# EDA_DriverBoardV1.net
KiCad netlist of a schematic drawn in EasyEDA
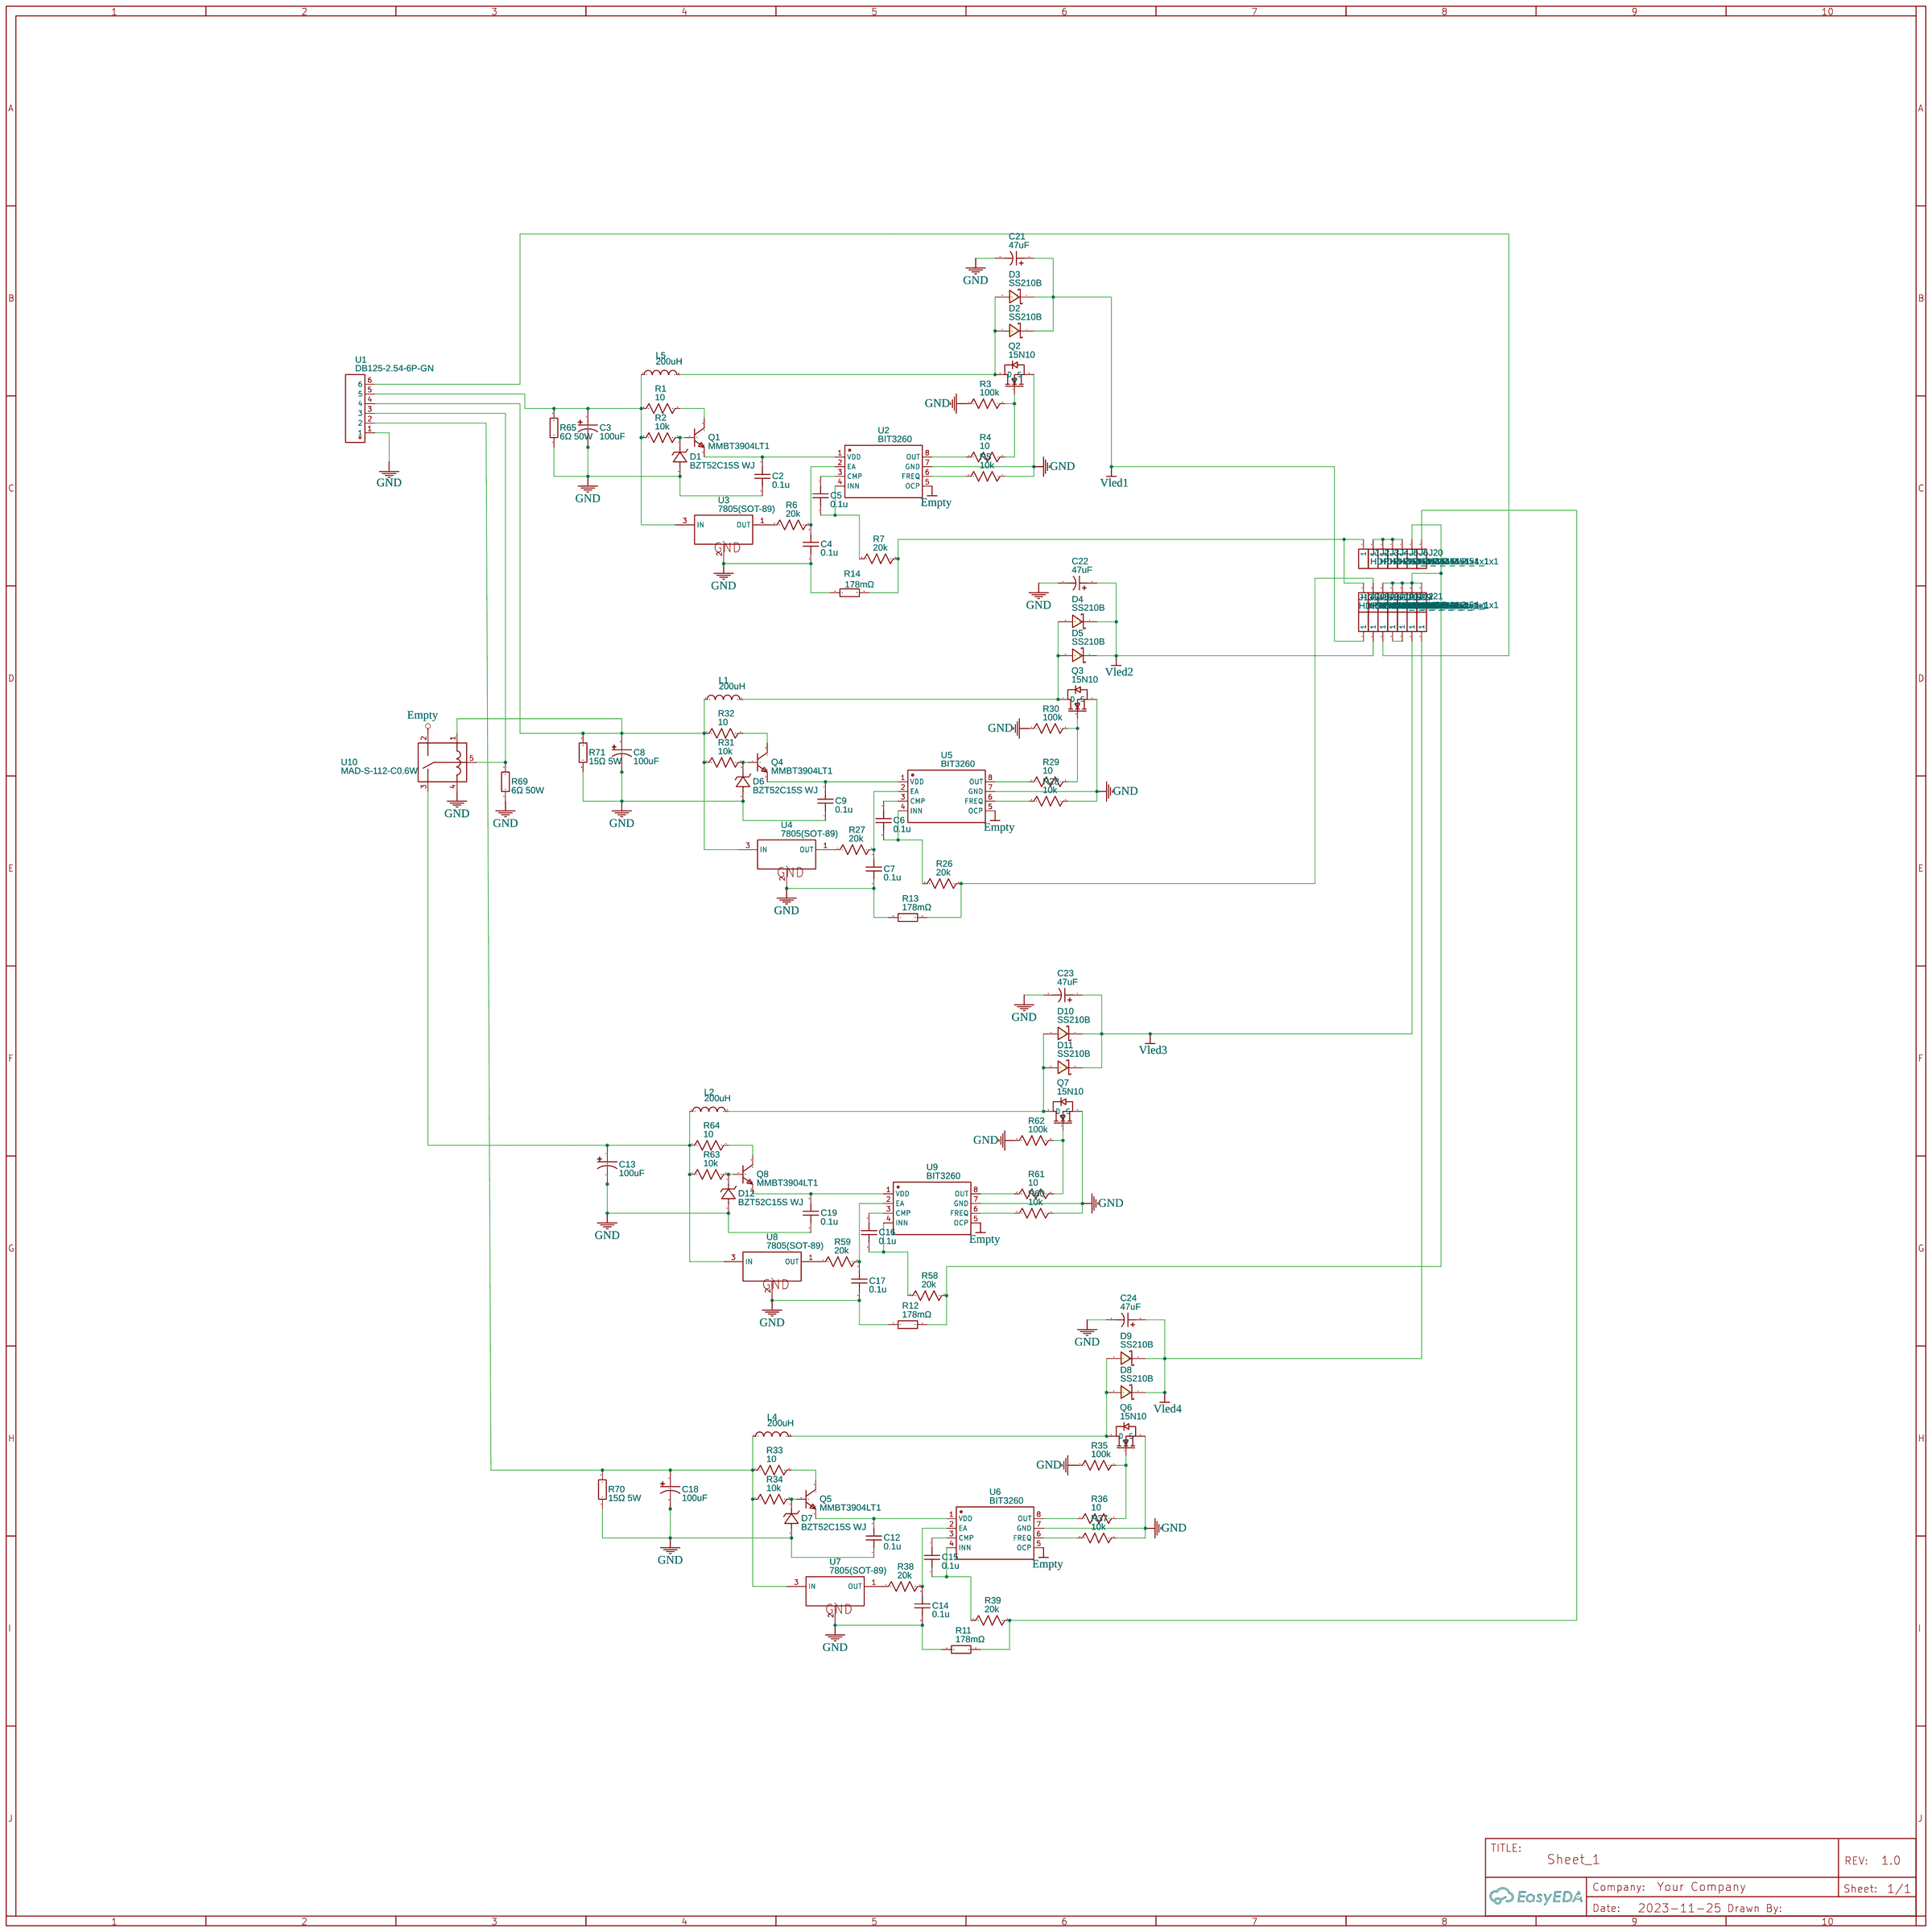
[diagram p0: schematic sheet]

(export (version "E")
  (design (tool "Eeschema 10.0.6"))
  (components
    (comp (ref "C2") (value "0.1u") (libsource (lib "") (part "C_0603_US")))
    (comp (ref "C3")
      (value "100uF")
      (fields
        (field (name "Manufacturer Part") "SPZ1HM101F09O00RAXXX")
        (field (name "Manufacturer") "AISHI(艾华集团)")
      )
      (libsource (lib "") (part "SPZ1HM101F09O00RAXXX_1"))
    )
    (comp (ref "C4") (value "0.1u") (libsource (lib "") (part "C_0603_US")))
    (comp (ref "C5") (value "0.1u") (libsource (lib "") (part "C_0603_US_1")))
    (comp (ref "C6") (value "0.1u") (libsource (lib "") (part "C_0603_US_1")))
    (comp (ref "C7") (value "0.1u") (libsource (lib "") (part "C_0603_US")))
    (comp (ref "C8")
      (value "100uF")
      (fields
        (field (name "Manufacturer Part") "SPZ1HM101F09O00RAXXX")
        (field (name "Manufacturer") "AISHI(艾华集团)")
      )
      (libsource (lib "") (part "SPZ1HM101F09O00RAXXX_1"))
    )
    (comp (ref "C9") (value "0.1u") (libsource (lib "") (part "C_0603_US")))
    (comp (ref "C12") (value "0.1u") (libsource (lib "") (part "C_0603_US")))
    (comp (ref "C13")
      (value "100uF")
      (fields
        (field (name "Manufacturer Part") "SPZ1HM101F09O00RAXXX")
        (field (name "Manufacturer") "AISHI(艾华集团)")
      )
      (libsource (lib "") (part "SPZ1HM101F09O00RAXXX"))
    )
    (comp (ref "C14") (value "0.1u") (libsource (lib "") (part "C_0603_US")))
    (comp (ref "C15") (value "0.1u") (libsource (lib "") (part "C_0603_US_1")))
    (comp (ref "C16") (value "0.1u") (libsource (lib "") (part "C_0603_US_1")))
    (comp (ref "C17") (value "0.1u") (libsource (lib "") (part "C_0603_US")))
    (comp (ref "C18")
      (value "100uF")
      (fields
        (field (name "Manufacturer Part") "SPZ1HM101F09O00RAXXX")
        (field (name "Manufacturer") "AISHI(艾华集团)")
      )
      (libsource (lib "") (part "SPZ1HM101F09O00RAXXX"))
    )
    (comp (ref "C19") (value "0.1u") (libsource (lib "") (part "C_0603_US")))
    (comp (ref "C21")
      (value "47uF")
      (fields
        (field (name "Manufacturer Part") "SPZ1KM470G12O00RAXXX")
        (field (name "Manufacturer") "AISHI(艾华集团)")
      )
      (libsource (lib "") (part "SPZ1KM470G12O00RAXXX_1"))
    )
    (comp (ref "C22")
      (value "47uF")
      (fields
        (field (name "Manufacturer Part") "SPZ1KM470G12O00RAXXX")
        (field (name "Manufacturer") "AISHI(艾华集团)")
      )
      (libsource (lib "") (part "SPZ1KM470G12O00RAXXX_1"))
    )
    (comp (ref "C23")
      (value "47uF")
      (fields
        (field (name "Manufacturer Part") "SPZ1KM470G12O00RAXXX")
        (field (name "Manufacturer") "AISHI(艾华集团)")
      )
      (libsource (lib "") (part "SPZ1KM470G12O00RAXXX"))
    )
    (comp (ref "C24")
      (value "47uF")
      (fields
        (field (name "Manufacturer Part") "SPZ1KM470G12O00RAXXX")
        (field (name "Manufacturer") "AISHI(艾华集团)")
      )
      (libsource (lib "") (part "SPZ1KM470G12O00RAXXX"))
    )
    (comp (ref "D1")
      (value "BZT52C15S WJ")
      (fields (field (name "Manufacturer") "CBI(创基)"))
      (libsource (lib "") (part "BZT52C15S WJ"))
    )
    (comp (ref "D2")
      (value "SS210B")
      (fields (field (name "Manufacturer") "晶导微电子"))
      (libsource (lib "") (part "SS210B"))
    )
    (comp (ref "D3")
      (value "SS210B")
      (fields (field (name "Manufacturer") "晶导微电子"))
      (libsource (lib "") (part "SS210B"))
    )
    (comp (ref "D4")
      (value "SS210B")
      (fields (field (name "Manufacturer") "晶导微电子"))
      (libsource (lib "") (part "SS210B"))
    )
    (comp (ref "D5")
      (value "SS210B")
      (fields (field (name "Manufacturer") "晶导微电子"))
      (libsource (lib "") (part "SS210B"))
    )
    (comp (ref "D6")
      (value "BZT52C15S WJ")
      (fields (field (name "Manufacturer") "CBI(创基)"))
      (libsource (lib "") (part "BZT52C15S WJ"))
    )
    (comp (ref "D7")
      (value "BZT52C15S WJ")
      (fields (field (name "Manufacturer") "CBI(创基)"))
      (libsource (lib "") (part "BZT52C15S WJ"))
    )
    (comp (ref "D8")
      (value "SS210B")
      (fields (field (name "Manufacturer") "晶导微电子"))
      (libsource (lib "") (part "SS210B"))
    )
    (comp (ref "D9")
      (value "SS210B")
      (fields (field (name "Manufacturer") "晶导微电子"))
      (libsource (lib "") (part "SS210B"))
    )
    (comp (ref "D10")
      (value "SS210B")
      (fields (field (name "Manufacturer") "晶导微电子"))
      (libsource (lib "") (part "SS210B"))
    )
    (comp (ref "D11")
      (value "SS210B")
      (fields (field (name "Manufacturer") "晶导微电子"))
      (libsource (lib "") (part "SS210B"))
    )
    (comp (ref "D12")
      (value "BZT52C15S WJ")
      (fields (field (name "Manufacturer") "CBI(创基)"))
      (libsource (lib "") (part "BZT52C15S WJ"))
    )
    (comp (ref "J1") (value "HDR-M-2.54_1x1") (libsource (lib "") (part "HDR-M-2.54_1x1_1")))
    (comp (ref "J2") (value "HDR-M-2.54_1x1") (libsource (lib "") (part "HDR-M-2.54_1x1_1")))
    (comp (ref "J3") (value "HDR-M-2.54_1x1") (libsource (lib "") (part "HDR-M-2.54_1x1_1")))
    (comp (ref "J4") (value "HDR-M-2.54_1x1") (libsource (lib "") (part "HDR-M-2.54_1x1_1")))
    (comp (ref "J5") (value "HDR-M-2.54_1x1") (libsource (lib "") (part "HDR-M-2.54_1x1_1")))
    (comp (ref "J6") (value "HDR-M-2.54_1x1") (libsource (lib "") (part "HDR-M-2.54_1x1_1")))
    (comp (ref "J7") (value "HDR-M-2.54_1x1") (libsource (lib "") (part "HDR-M-2.54_1x1_1")))
    (comp (ref "J8") (value "HDR-M-2.54_1x1") (libsource (lib "") (part "HDR-M-2.54_1x1_1")))
    (comp (ref "J9") (value "HDR-M-2.54_1x1") (libsource (lib "") (part "HDR-M-2.54_1x1_1")))
    (comp (ref "J10") (value "HDR-M-2.54_1x1") (libsource (lib "") (part "HDR-M-2.54_1x1_1")))
    (comp (ref "J11") (value "HDR-M-2.54_1x1") (libsource (lib "") (part "HDR-M-2.54_1x1_1")))
    (comp (ref "J12") (value "HDR-M-2.54_1x1") (libsource (lib "") (part "HDR-M-2.54_1x1_1")))
    (comp (ref "J13") (value "HDR-M-2.54_1x1") (libsource (lib "") (part "HDR-M-2.54_1x1")))
    (comp (ref "J14") (value "HDR-M-2.54_1x1") (libsource (lib "") (part "HDR-M-2.54_1x1")))
    (comp (ref "J15") (value "HDR-M-2.54_1x1") (libsource (lib "") (part "HDR-M-2.54_1x1")))
    (comp (ref "J16") (value "HDR-M-2.54_1x1") (libsource (lib "") (part "HDR-M-2.54_1x1")))
    (comp (ref "J17") (value "HDR-M-2.54_1x1") (libsource (lib "") (part "HDR-M-2.54_1x1")))
    (comp (ref "J18") (value "HDR-M-2.54_1x1") (libsource (lib "") (part "HDR-M-2.54_1x1")))
    (comp (ref "J19") (value "HDR-M-2.54_1x1") (libsource (lib "") (part "HDR-M-2.54_1x1")))
    (comp (ref "J20") (value "HDR-M-2.54_1x1") (libsource (lib "") (part "HDR-M-2.54_1x1_1")))
    (comp (ref "J21") (value "HDR-M-2.54_1x1") (libsource (lib "") (part "HDR-M-2.54_1x1_1")))
    (comp (ref "L1")
      (value "200uH")
      (fields (field (name "Manufacturer Part") "FNR5020S201MT") (field (name "Manufacturer") "cjiang(长江微电)"))
      (libsource (lib "") (part "FNR5020S201MT"))
    )
    (comp (ref "L2")
      (value "200uH")
      (fields (field (name "Manufacturer Part") "FNR5020S201MT") (field (name "Manufacturer") "cjiang(长江微电)"))
      (libsource (lib "") (part "FNR5020S201MT"))
    )
    (comp (ref "L4")
      (value "200uH")
      (fields (field (name "Manufacturer Part") "FNR5020S201MT") (field (name "Manufacturer") "cjiang(长江微电)"))
      (libsource (lib "") (part "FNR5020S201MT"))
    )
    (comp (ref "L5")
      (value "200uH")
      (fields (field (name "Manufacturer Part") "FNR5020S201MT") (field (name "Manufacturer") "cjiang(长江微电)"))
      (libsource (lib "") (part "FNR5020S201MT"))
    )
    (comp (ref "Q1")
      (value "MMBT3904LT1")
      (fields (field (name "Manufacturer") "LGE(鲁光)"))
      (libsource (lib "") (part "MMBT3904LT1"))
    )
    (comp (ref "Q2")
      (value "15N10")
      (fields (field (name "Manufacturer") "TF(拓锋)"))
      (libsource (lib "") (part "15N10"))
    )
    (comp (ref "Q3")
      (value "15N10")
      (fields (field (name "Manufacturer") "TF(拓锋)"))
      (libsource (lib "") (part "15N10"))
    )
    (comp (ref "Q4")
      (value "MMBT3904LT1")
      (fields (field (name "Manufacturer") "LGE(鲁光)"))
      (libsource (lib "") (part "MMBT3904LT1"))
    )
    (comp (ref "Q5")
      (value "MMBT3904LT1")
      (fields (field (name "Manufacturer") "LGE(鲁光)"))
      (libsource (lib "") (part "MMBT3904LT1"))
    )
    (comp (ref "Q6")
      (value "15N10")
      (fields (field (name "Manufacturer") "TF(拓锋)"))
      (libsource (lib "") (part "15N10"))
    )
    (comp (ref "Q7")
      (value "15N10")
      (fields (field (name "Manufacturer") "TF(拓锋)"))
      (libsource (lib "") (part "15N10"))
    )
    (comp (ref "Q8")
      (value "MMBT3904LT1")
      (fields (field (name "Manufacturer") "LGE(鲁光)"))
      (libsource (lib "") (part "MMBT3904LT1"))
    )
    (comp (ref "R1") (value "10") (libsource (lib "") (part "R_0603_US")))
    (comp (ref "R2") (value "10k") (libsource (lib "") (part "R_0603_US")))
    (comp (ref "R3") (value "100k") (libsource (lib "") (part "R_0603_US")))
    (comp (ref "R4") (value "10") (libsource (lib "") (part "R_0603_US")))
    (comp (ref "R5") (value "10k") (libsource (lib "") (part "R_0603_US_1")))
    (comp (ref "R6") (value "20k") (libsource (lib "") (part "R_0603_US")))
    (comp (ref "R7") (value "20k") (libsource (lib "") (part "R_0603_US_1")))
    (comp (ref "R11")
      (value "178mΩ")
      (fields (field (name "Manufacturer Part") "RTT06R180FTP") (field (name "Manufacturer") "RALEC(旺诠)"))
      (libsource (lib "") (part "RTT06R180FTP"))
    )
    (comp (ref "R12")
      (value "178mΩ")
      (fields (field (name "Manufacturer Part") "RTT06R180FTP") (field (name "Manufacturer") "RALEC(旺诠)"))
      (libsource (lib "") (part "RTT06R180FTP"))
    )
    (comp (ref "R13")
      (value "178mΩ")
      (fields (field (name "Manufacturer Part") "RTT06R180FTP") (field (name "Manufacturer") "RALEC(旺诠)"))
      (libsource (lib "") (part "RTT06R180FTP"))
    )
    (comp (ref "R14")
      (value "178mΩ")
      (fields (field (name "Manufacturer Part") "RTT06R180FTP") (field (name "Manufacturer") "RALEC(旺诠)"))
      (libsource (lib "") (part "RTT06R180FTP"))
    )
    (comp (ref "R26") (value "20k") (libsource (lib "") (part "R_0603_US_1")))
    (comp (ref "R27") (value "20k") (libsource (lib "") (part "R_0603_US")))
    (comp (ref "R28") (value "10k") (libsource (lib "") (part "R_0603_US_1")))
    (comp (ref "R29") (value "10") (libsource (lib "") (part "R_0603_US")))
    (comp (ref "R30") (value "100k") (libsource (lib "") (part "R_0603_US")))
    (comp (ref "R31") (value "10k") (libsource (lib "") (part "R_0603_US")))
    (comp (ref "R32") (value "10") (libsource (lib "") (part "R_0603_US")))
    (comp (ref "R33") (value "10") (libsource (lib "") (part "R_0603_US")))
    (comp (ref "R34") (value "10k") (libsource (lib "") (part "R_0603_US")))
    (comp (ref "R35") (value "100k") (libsource (lib "") (part "R_0603_US")))
    (comp (ref "R36") (value "10") (libsource (lib "") (part "R_0603_US")))
    (comp (ref "R37") (value "10k") (libsource (lib "") (part "R_0603_US_1")))
    (comp (ref "R38") (value "20k") (libsource (lib "") (part "R_0603_US")))
    (comp (ref "R39") (value "20k") (libsource (lib "") (part "R_0603_US_1")))
    (comp (ref "R58") (value "20k") (libsource (lib "") (part "R_0603_US_1")))
    (comp (ref "R59") (value "20k") (libsource (lib "") (part "R_0603_US")))
    (comp (ref "R60") (value "10k") (libsource (lib "") (part "R_0603_US_1")))
    (comp (ref "R61") (value "10") (libsource (lib "") (part "R_0603_US")))
    (comp (ref "R62") (value "100k") (libsource (lib "") (part "R_0603_US")))
    (comp (ref "R63") (value "10k") (libsource (lib "") (part "R_0603_US")))
    (comp (ref "R64") (value "10") (libsource (lib "") (part "R_0603_US")))
    (comp (ref "R65")
      (value "6Ω 50W")
      (fields
        (field (name "Manufacturer Part") "CFR0W4J0120A50")
        (field (name "Manufacturer") "UNI-ROYAL(厚声)")
      )
      (libsource (lib "") (part "CFR0W4J0120A50"))
    )
    (comp (ref "R69")
      (value "6Ω 50W")
      (fields
        (field (name "Manufacturer Part") "CFR0W4J0120A50")
        (field (name "Manufacturer") "UNI-ROYAL(厚声)")
      )
      (libsource (lib "") (part "CFR0W4J0120A50"))
    )
    (comp (ref "R70")
      (value "15Ω 5W")
      (fields
        (field (name "Manufacturer Part") "CFR0W4J0120A50")
        (field (name "Manufacturer") "UNI-ROYAL(厚声)")
      )
      (libsource (lib "") (part "CFR0W4J0120A50"))
    )
    (comp (ref "R71")
      (value "15Ω 5W")
      (fields
        (field (name "Manufacturer Part") "CFR0W4J0120A50")
        (field (name "Manufacturer") "UNI-ROYAL(厚声)")
      )
      (libsource (lib "") (part "CFR0W4J0120A50"))
    )
    (comp (ref "U1")
      (value "DB125-2.54-6P-GN")
      (fields
        (field (name "Manufacturer Part") "DB125-2.54-6P-GN-S")
        (field (name "Manufacturer") "DIBO(地博电气)")
      )
      (libsource (lib "") (part "DB125-2.54-6P-GN"))
    )
    (comp (ref "U2") (value "BIT3260") (libsource (lib "") (part "BIT3260")))
    (comp (ref "U3")
      (value "7805(SOT-89)")
      (fields (field (name "Manufacturer Part") "CJ78L05") (field (name "Manufacturer") "CJ"))
      (libsource (lib "") (part "7805(SOT-89)"))
    )
    (comp (ref "U4")
      (value "7805(SOT-89)")
      (fields (field (name "Manufacturer Part") "CJ78L05") (field (name "Manufacturer") "CJ"))
      (libsource (lib "") (part "7805(SOT-89)"))
    )
    (comp (ref "U5") (value "BIT3260") (libsource (lib "") (part "BIT3260")))
    (comp (ref "U6") (value "BIT3260") (libsource (lib "") (part "BIT3260")))
    (comp (ref "U7")
      (value "7805(SOT-89)")
      (fields (field (name "Manufacturer Part") "CJ78L05") (field (name "Manufacturer") "CJ"))
      (libsource (lib "") (part "7805(SOT-89)"))
    )
    (comp (ref "U8")
      (value "7805(SOT-89)")
      (fields (field (name "Manufacturer Part") "CJ78L05") (field (name "Manufacturer") "CJ"))
      (libsource (lib "") (part "7805(SOT-89)"))
    )
    (comp (ref "U9") (value "BIT3260") (libsource (lib "") (part "BIT3260")))
    (comp (ref "U10")
      (value "MAD-S-112-C0.6W")
      (fields (field (name "Manufacturer") "MEISHUO(美硕)"))
      (libsource (lib "") (part "MAD-S-112-C0.6W"))
    )
  )
  (nets
    (net (code "1") (name "Empty") (class "Default")
      (node (ref "U10") (pin "2") (pinfunction "2_2") (pintype "unspecified"))
      (node (ref "U2") (pin "5") (pinfunction "OCP_5") (pintype "unspecified"))
      (node (ref "U5") (pin "5") (pinfunction "OCP_5") (pintype "unspecified"))
      (node (ref "U6") (pin "5") (pinfunction "OCP_5") (pintype "unspecified"))
      (node (ref "U9") (pin "5") (pinfunction "OCP_5") (pintype "unspecified"))
    )
    (net (code "2") (name "GND") (class "Default")
      (node (ref "C12") (pin "1") (pinfunction "1_1") (pintype "unspecified"))
      (node (ref "C13") (pin "2") (pinfunction "2_2") (pintype "unspecified"))
      (node (ref "C14") (pin "1") (pinfunction "1_1") (pintype "unspecified"))
      (node (ref "C17") (pin "1") (pinfunction "1_1") (pintype "unspecified"))
      (node (ref "C18") (pin "2") (pinfunction "2_2") (pintype "unspecified"))
      (node (ref "C19") (pin "1") (pinfunction "1_1") (pintype "unspecified"))
      (node (ref "C2") (pin "1") (pinfunction "1_1") (pintype "unspecified"))
      (node (ref "C21") (pin "2") (pinfunction "2_2") (pintype "input"))
      (node (ref "C22") (pin "2") (pinfunction "2_2") (pintype "input"))
      (node (ref "C23") (pin "2") (pinfunction "2_2") (pintype "input"))
      (node (ref "C24") (pin "2") (pinfunction "2_2") (pintype "input"))
      (node (ref "C3") (pin "2") (pinfunction "2_2") (pintype "unspecified"))
      (node (ref "C4") (pin "1") (pinfunction "1_1") (pintype "unspecified"))
      (node (ref "C7") (pin "1") (pinfunction "1_1") (pintype "unspecified"))
      (node (ref "C8") (pin "2") (pinfunction "2_2") (pintype "unspecified"))
      (node (ref "C9") (pin "1") (pinfunction "1_1") (pintype "unspecified"))
      (node (ref "D1") (pin "2") (pinfunction "A_2") (pintype "unspecified"))
      (node (ref "D12") (pin "2") (pinfunction "A_2") (pintype "unspecified"))
      (node (ref "D6") (pin "2") (pinfunction "A_2") (pintype "unspecified"))
      (node (ref "D7") (pin "2") (pinfunction "A_2") (pintype "unspecified"))
      (node (ref "Q2") (pin "3") (pinfunction "S_3") (pintype "unspecified"))
      (node (ref "Q3") (pin "3") (pinfunction "S_3") (pintype "unspecified"))
      (node (ref "Q6") (pin "3") (pinfunction "S_3") (pintype "unspecified"))
      (node (ref "Q7") (pin "3") (pinfunction "S_3") (pintype "unspecified"))
      (node (ref "R11") (pin "1") (pinfunction "1_1") (pintype "input"))
      (node (ref "R12") (pin "1") (pinfunction "1_1") (pintype "input"))
      (node (ref "R13") (pin "1") (pinfunction "1_1") (pintype "input"))
      (node (ref "R14") (pin "1") (pinfunction "1_1") (pintype "input"))
      (node (ref "R28") (pin "1") (pinfunction "1_1") (pintype "unspecified"))
      (node (ref "R3") (pin "1") (pinfunction "1_1") (pintype "unspecified"))
      (node (ref "R30") (pin "1") (pinfunction "1_1") (pintype "unspecified"))
      (node (ref "R35") (pin "1") (pinfunction "1_1") (pintype "unspecified"))
      (node (ref "R37") (pin "1") (pinfunction "1_1") (pintype "unspecified"))
      (node (ref "R5") (pin "1") (pinfunction "1_1") (pintype "unspecified"))
      (node (ref "R60") (pin "1") (pinfunction "1_1") (pintype "unspecified"))
      (node (ref "R62") (pin "1") (pinfunction "1_1") (pintype "unspecified"))
      (node (ref "R65") (pin "1") (pinfunction "1_1") (pintype "input"))
      (node (ref "R69") (pin "1") (pinfunction "1_1") (pintype "input"))
      (node (ref "R70") (pin "1") (pinfunction "1_1") (pintype "input"))
      (node (ref "R71") (pin "1") (pinfunction "1_1") (pintype "input"))
      (node (ref "U1") (pin "1") (pinfunction "1_1") (pintype "unspecified"))
      (node (ref "U10") (pin "4") (pinfunction "4_4") (pintype "unspecified"))
      (node (ref "U2") (pin "7") (pinfunction "GND_7") (pintype "unspecified"))
      (node (ref "U3") (pin "2") (pinfunction "GND_2") (pintype "passive"))
      (node (ref "U4") (pin "2") (pinfunction "GND_2") (pintype "passive"))
      (node (ref "U5") (pin "7") (pinfunction "GND_7") (pintype "unspecified"))
      (node (ref "U6") (pin "7") (pinfunction "GND_7") (pintype "unspecified"))
      (node (ref "U7") (pin "2") (pinfunction "GND_2") (pintype "passive"))
      (node (ref "U8") (pin "2") (pinfunction "GND_2") (pintype "passive"))
      (node (ref "U9") (pin "7") (pinfunction "GND_7") (pintype "unspecified"))
    )
    (net (code "3") (name "Net-(D1-K)") (class "Default")
      (node (ref "D1") (pin "1") (pinfunction "K_1") (pintype "unspecified"))
      (node (ref "Q1") (pin "1") (pinfunction "B_1") (pintype "unspecified"))
      (node (ref "R2") (pin "2") (pinfunction "2_2") (pintype "unspecified"))
    )
    (net (code "4") (name "Net-(D2-A)") (class "Default")
      (node (ref "D2") (pin "2") (pinfunction "A_2") (pintype "unspecified"))
      (node (ref "D3") (pin "2") (pinfunction "A_2") (pintype "unspecified"))
      (node (ref "L5") (pin "2") (pinfunction "2_2") (pintype "unspecified"))
      (node (ref "Q2") (pin "2") (pinfunction "D_2") (pintype "unspecified"))
    )
    (net (code "5") (name "Net-(D4-A)") (class "Default")
      (node (ref "D4") (pin "2") (pinfunction "A_2") (pintype "unspecified"))
      (node (ref "D5") (pin "2") (pinfunction "A_2") (pintype "unspecified"))
      (node (ref "L1") (pin "2") (pinfunction "2_2") (pintype "unspecified"))
      (node (ref "Q3") (pin "2") (pinfunction "D_2") (pintype "unspecified"))
    )
    (net (code "6") (name "Net-(D6-K)") (class "Default")
      (node (ref "D6") (pin "1") (pinfunction "K_1") (pintype "unspecified"))
      (node (ref "Q4") (pin "1") (pinfunction "B_1") (pintype "unspecified"))
      (node (ref "R31") (pin "2") (pinfunction "2_2") (pintype "unspecified"))
    )
    (net (code "7") (name "Net-(D7-K)") (class "Default")
      (node (ref "D7") (pin "1") (pinfunction "K_1") (pintype "unspecified"))
      (node (ref "Q5") (pin "1") (pinfunction "B_1") (pintype "unspecified"))
      (node (ref "R34") (pin "2") (pinfunction "2_2") (pintype "unspecified"))
    )
    (net (code "8") (name "Net-(D8-A)") (class "Default")
      (node (ref "D8") (pin "2") (pinfunction "A_2") (pintype "unspecified"))
      (node (ref "D9") (pin "2") (pinfunction "A_2") (pintype "unspecified"))
      (node (ref "L4") (pin "2") (pinfunction "2_2") (pintype "unspecified"))
      (node (ref "Q6") (pin "2") (pinfunction "D_2") (pintype "unspecified"))
    )
    (net (code "9") (name "Net-(D10-A)") (class "Default")
      (node (ref "D10") (pin "2") (pinfunction "A_2") (pintype "unspecified"))
      (node (ref "D11") (pin "2") (pinfunction "A_2") (pintype "unspecified"))
      (node (ref "L2") (pin "2") (pinfunction "2_2") (pintype "unspecified"))
      (node (ref "Q7") (pin "2") (pinfunction "D_2") (pintype "unspecified"))
    )
    (net (code "10") (name "Net-(D12-K)") (class "Default")
      (node (ref "D12") (pin "1") (pinfunction "K_1") (pintype "unspecified"))
      (node (ref "Q8") (pin "1") (pinfunction "B_1") (pintype "unspecified"))
      (node (ref "R63") (pin "2") (pinfunction "2_2") (pintype "unspecified"))
    )
    (net (code "11") (name "Net-(J1-Pad1)") (class "Default")
      (node (ref "J1") (pin "1") (pinfunction "1_1") (pintype "input"))
      (node (ref "J7") (pin "1") (pinfunction "1_1") (pintype "input"))
      (node (ref "R14") (pin "2") (pinfunction "2_2") (pintype "input"))
      (node (ref "R7") (pin "1") (pinfunction "1_1") (pintype "unspecified"))
    )
    (net (code "12") (name "Net-(J2-Pad1)") (class "Default")
      (node (ref "J2") (pin "1") (pinfunction "1_1") (pintype "input"))
      (node (ref "J3") (pin "1") (pinfunction "1_1") (pintype "input"))
      (node (ref "J4") (pin "1") (pinfunction "1_1") (pintype "input"))
      (node (ref "J5") (pin "1") (pinfunction "1_1") (pintype "input"))
    )
    (net (code "13") (name "Net-(J8-Pad1)") (class "Default")
      (node (ref "J8") (pin "1") (pinfunction "1_1") (pintype "input"))
      (node (ref "R13") (pin "2") (pinfunction "2_2") (pintype "input"))
      (node (ref "R26") (pin "1") (pinfunction "1_1") (pintype "unspecified"))
    )
    (net (code "14") (name "Net-(J10-Pad1)") (class "Default")
      (node (ref "J10") (pin "1") (pinfunction "1_1") (pintype "input"))
      (node (ref "J11") (pin "1") (pinfunction "1_1") (pintype "input"))
      (node (ref "J12") (pin "1") (pinfunction "1_1") (pintype "input"))
      (node (ref "J21") (pin "1") (pinfunction "1_1") (pintype "input"))
      (node (ref "J6") (pin "1") (pinfunction "1_1") (pintype "input"))
      (node (ref "J9") (pin "1") (pinfunction "1_1") (pintype "input"))
      (node (ref "R12") (pin "2") (pinfunction "2_2") (pintype "input"))
      (node (ref "R58") (pin "1") (pinfunction "1_1") (pintype "unspecified"))
    )
    (net (code "15") (name "Net-(J15-Pad1)") (class "Default")
      (node (ref "J15") (pin "1") (pinfunction "1_1") (pintype "input"))
      (node (ref "U1") (pin "6") (pinfunction "6_6") (pintype "unspecified"))
    )
    (net (code "16") (name "Net-(J16-Pad1)") (class "Default")
      (node (ref "J16") (pin "1") (pinfunction "1_1") (pintype "input"))
      (node (ref "J17") (pin "1") (pinfunction "1_1") (pintype "input"))
    )
    (net (code "17") (name "Net-(J20-Pad1)") (class "Default")
      (node (ref "J20") (pin "1") (pinfunction "1_1") (pintype "input"))
      (node (ref "R11") (pin "2") (pinfunction "2_2") (pintype "input"))
      (node (ref "R39") (pin "1") (pinfunction "1_1") (pintype "unspecified"))
    )
    (net (code "18") (name "Net-(Q1-C)") (class "Default")
      (node (ref "Q1") (pin "3") (pinfunction "C_3") (pintype "unspecified"))
      (node (ref "R1") (pin "2") (pinfunction "2_2") (pintype "unspecified"))
    )
    (net (code "19") (name "Net-(Q1-E)") (class "Default")
      (node (ref "C2") (pin "2") (pinfunction "2_2") (pintype "unspecified"))
      (node (ref "Q1") (pin "2") (pinfunction "E_2") (pintype "unspecified"))
      (node (ref "U2") (pin "1") (pinfunction "VDD_1") (pintype "unspecified"))
    )
    (net (code "20") (name "Net-(Q2-G)") (class "Default")
      (node (ref "Q2") (pin "1") (pinfunction "G_1") (pintype "unspecified"))
      (node (ref "R3") (pin "2") (pinfunction "2_2") (pintype "unspecified"))
      (node (ref "R4") (pin "2") (pinfunction "2_2") (pintype "unspecified"))
    )
    (net (code "21") (name "Net-(Q3-G)") (class "Default")
      (node (ref "Q3") (pin "1") (pinfunction "G_1") (pintype "unspecified"))
      (node (ref "R29") (pin "2") (pinfunction "2_2") (pintype "unspecified"))
      (node (ref "R30") (pin "2") (pinfunction "2_2") (pintype "unspecified"))
    )
    (net (code "22") (name "Net-(Q4-C)") (class "Default")
      (node (ref "Q4") (pin "3") (pinfunction "C_3") (pintype "unspecified"))
      (node (ref "R32") (pin "2") (pinfunction "2_2") (pintype "unspecified"))
    )
    (net (code "23") (name "Net-(Q4-E)") (class "Default")
      (node (ref "C9") (pin "2") (pinfunction "2_2") (pintype "unspecified"))
      (node (ref "Q4") (pin "2") (pinfunction "E_2") (pintype "unspecified"))
      (node (ref "U5") (pin "1") (pinfunction "VDD_1") (pintype "unspecified"))
    )
    (net (code "24") (name "Net-(Q5-C)") (class "Default")
      (node (ref "Q5") (pin "3") (pinfunction "C_3") (pintype "unspecified"))
      (node (ref "R33") (pin "2") (pinfunction "2_2") (pintype "unspecified"))
    )
    (net (code "25") (name "Net-(Q5-E)") (class "Default")
      (node (ref "C12") (pin "2") (pinfunction "2_2") (pintype "unspecified"))
      (node (ref "Q5") (pin "2") (pinfunction "E_2") (pintype "unspecified"))
      (node (ref "U6") (pin "1") (pinfunction "VDD_1") (pintype "unspecified"))
    )
    (net (code "26") (name "Net-(Q6-G)") (class "Default")
      (node (ref "Q6") (pin "1") (pinfunction "G_1") (pintype "unspecified"))
      (node (ref "R35") (pin "2") (pinfunction "2_2") (pintype "unspecified"))
      (node (ref "R36") (pin "2") (pinfunction "2_2") (pintype "unspecified"))
    )
    (net (code "27") (name "Net-(Q7-G)") (class "Default")
      (node (ref "Q7") (pin "1") (pinfunction "G_1") (pintype "unspecified"))
      (node (ref "R61") (pin "2") (pinfunction "2_2") (pintype "unspecified"))
      (node (ref "R62") (pin "2") (pinfunction "2_2") (pintype "unspecified"))
    )
    (net (code "28") (name "Net-(Q8-C)") (class "Default")
      (node (ref "Q8") (pin "3") (pinfunction "C_3") (pintype "unspecified"))
      (node (ref "R64") (pin "2") (pinfunction "2_2") (pintype "unspecified"))
    )
    (net (code "29") (name "Net-(Q8-E)") (class "Default")
      (node (ref "C19") (pin "2") (pinfunction "2_2") (pintype "unspecified"))
      (node (ref "Q8") (pin "2") (pinfunction "E_2") (pintype "unspecified"))
      (node (ref "U9") (pin "1") (pinfunction "VDD_1") (pintype "unspecified"))
    )
    (net (code "30") (name "Net-(R69-Pad2)") (class "Default")
      (node (ref "R69") (pin "2") (pinfunction "2_2") (pintype "input"))
      (node (ref "U1") (pin "3") (pinfunction "3_3") (pintype "unspecified"))
      (node (ref "U10") (pin "5") (pinfunction "5_5") (pintype "unspecified"))
    )
    (net (code "31") (name "Net-(U2-CMP)") (class "Default")
      (node (ref "C5") (pin "1") (pinfunction "1_1") (pintype "unspecified"))
      (node (ref "U2") (pin "3") (pinfunction "CMP_3") (pintype "unspecified"))
    )
    (net (code "32") (name "Net-(U2-EA)") (class "Default")
      (node (ref "C4") (pin "2") (pinfunction "2_2") (pintype "unspecified"))
      (node (ref "R6") (pin "2") (pinfunction "2_2") (pintype "unspecified"))
      (node (ref "U2") (pin "2") (pinfunction "EA_2") (pintype "unspecified"))
    )
    (net (code "33") (name "Net-(U2-FREQ)") (class "Default")
      (node (ref "R5") (pin "2") (pinfunction "2_2") (pintype "unspecified"))
      (node (ref "U2") (pin "6") (pinfunction "FREQ_6") (pintype "unspecified"))
    )
    (net (code "34") (name "Net-(U2-INN)") (class "Default")
      (node (ref "C5") (pin "2") (pinfunction "2_2") (pintype "unspecified"))
      (node (ref "R7") (pin "2") (pinfunction "2_2") (pintype "unspecified"))
      (node (ref "U2") (pin "4") (pinfunction "INN_4") (pintype "unspecified"))
    )
    (net (code "35") (name "Net-(U2-OUT)") (class "Default")
      (node (ref "R4") (pin "1") (pinfunction "1_1") (pintype "unspecified"))
      (node (ref "U2") (pin "8") (pinfunction "OUT_8") (pintype "unspecified"))
    )
    (net (code "36") (name "Net-(U3-IN)") (class "Default")
      (node (ref "C3") (pin "1") (pinfunction "1_1") (pintype "unspecified"))
      (node (ref "L5") (pin "1") (pinfunction "1_1") (pintype "unspecified"))
      (node (ref "R1") (pin "1") (pinfunction "1_1") (pintype "unspecified"))
      (node (ref "R2") (pin "1") (pinfunction "1_1") (pintype "unspecified"))
      (node (ref "R65") (pin "2") (pinfunction "2_2") (pintype "input"))
      (node (ref "U1") (pin "5") (pinfunction "5_5") (pintype "unspecified"))
      (node (ref "U3") (pin "3") (pinfunction "IN_3") (pintype "passive"))
    )
    (net (code "37") (name "Net-(U3-OUT)") (class "Default")
      (node (ref "R6") (pin "1") (pinfunction "1_1") (pintype "unspecified"))
      (node (ref "U3") (pin "1") (pinfunction "OUT_1") (pintype "passive"))
    )
    (net (code "38") (name "Net-(U4-IN)") (class "Default")
      (node (ref "C8") (pin "1") (pinfunction "1_1") (pintype "unspecified"))
      (node (ref "L1") (pin "1") (pinfunction "1_1") (pintype "unspecified"))
      (node (ref "R31") (pin "1") (pinfunction "1_1") (pintype "unspecified"))
      (node (ref "R32") (pin "1") (pinfunction "1_1") (pintype "unspecified"))
      (node (ref "R71") (pin "2") (pinfunction "2_2") (pintype "input"))
      (node (ref "U1") (pin "4") (pinfunction "4_4") (pintype "unspecified"))
      (node (ref "U10") (pin "1") (pinfunction "1_1") (pintype "unspecified"))
      (node (ref "U4") (pin "3") (pinfunction "IN_3") (pintype "passive"))
    )
    (net (code "39") (name "Net-(U4-OUT)") (class "Default")
      (node (ref "R27") (pin "1") (pinfunction "1_1") (pintype "unspecified"))
      (node (ref "U4") (pin "1") (pinfunction "OUT_1") (pintype "passive"))
    )
    (net (code "40") (name "Net-(U5-CMP)") (class "Default")
      (node (ref "C6") (pin "1") (pinfunction "1_1") (pintype "unspecified"))
      (node (ref "U5") (pin "3") (pinfunction "CMP_3") (pintype "unspecified"))
    )
    (net (code "41") (name "Net-(U5-EA)") (class "Default")
      (node (ref "C7") (pin "2") (pinfunction "2_2") (pintype "unspecified"))
      (node (ref "R27") (pin "2") (pinfunction "2_2") (pintype "unspecified"))
      (node (ref "U5") (pin "2") (pinfunction "EA_2") (pintype "unspecified"))
    )
    (net (code "42") (name "Net-(U5-FREQ)") (class "Default")
      (node (ref "R28") (pin "2") (pinfunction "2_2") (pintype "unspecified"))
      (node (ref "U5") (pin "6") (pinfunction "FREQ_6") (pintype "unspecified"))
    )
    (net (code "43") (name "Net-(U5-INN)") (class "Default")
      (node (ref "C6") (pin "2") (pinfunction "2_2") (pintype "unspecified"))
      (node (ref "R26") (pin "2") (pinfunction "2_2") (pintype "unspecified"))
      (node (ref "U5") (pin "4") (pinfunction "INN_4") (pintype "unspecified"))
    )
    (net (code "44") (name "Net-(U5-OUT)") (class "Default")
      (node (ref "R29") (pin "1") (pinfunction "1_1") (pintype "unspecified"))
      (node (ref "U5") (pin "8") (pinfunction "OUT_8") (pintype "unspecified"))
    )
    (net (code "45") (name "Net-(U6-CMP)") (class "Default")
      (node (ref "C15") (pin "1") (pinfunction "1_1") (pintype "unspecified"))
      (node (ref "U6") (pin "3") (pinfunction "CMP_3") (pintype "unspecified"))
    )
    (net (code "46") (name "Net-(U6-EA)") (class "Default")
      (node (ref "C14") (pin "2") (pinfunction "2_2") (pintype "unspecified"))
      (node (ref "R38") (pin "2") (pinfunction "2_2") (pintype "unspecified"))
      (node (ref "U6") (pin "2") (pinfunction "EA_2") (pintype "unspecified"))
    )
    (net (code "47") (name "Net-(U6-FREQ)") (class "Default")
      (node (ref "R37") (pin "2") (pinfunction "2_2") (pintype "unspecified"))
      (node (ref "U6") (pin "6") (pinfunction "FREQ_6") (pintype "unspecified"))
    )
    (net (code "48") (name "Net-(U6-INN)") (class "Default")
      (node (ref "C15") (pin "2") (pinfunction "2_2") (pintype "unspecified"))
      (node (ref "R39") (pin "2") (pinfunction "2_2") (pintype "unspecified"))
      (node (ref "U6") (pin "4") (pinfunction "INN_4") (pintype "unspecified"))
    )
    (net (code "49") (name "Net-(U6-OUT)") (class "Default")
      (node (ref "R36") (pin "1") (pinfunction "1_1") (pintype "unspecified"))
      (node (ref "U6") (pin "8") (pinfunction "OUT_8") (pintype "unspecified"))
    )
    (net (code "50") (name "Net-(U7-IN)") (class "Default")
      (node (ref "C18") (pin "1") (pinfunction "1_1") (pintype "unspecified"))
      (node (ref "L4") (pin "1") (pinfunction "1_1") (pintype "unspecified"))
      (node (ref "R33") (pin "1") (pinfunction "1_1") (pintype "unspecified"))
      (node (ref "R34") (pin "1") (pinfunction "1_1") (pintype "unspecified"))
      (node (ref "R70") (pin "2") (pinfunction "2_2") (pintype "input"))
      (node (ref "U1") (pin "2") (pinfunction "2_2") (pintype "unspecified"))
      (node (ref "U7") (pin "3") (pinfunction "IN_3") (pintype "passive"))
    )
    (net (code "51") (name "Net-(U7-OUT)") (class "Default")
      (node (ref "R38") (pin "1") (pinfunction "1_1") (pintype "unspecified"))
      (node (ref "U7") (pin "1") (pinfunction "OUT_1") (pintype "passive"))
    )
    (net (code "52") (name "Net-(U8-IN)") (class "Default")
      (node (ref "C13") (pin "1") (pinfunction "1_1") (pintype "unspecified"))
      (node (ref "L2") (pin "1") (pinfunction "1_1") (pintype "unspecified"))
      (node (ref "R63") (pin "1") (pinfunction "1_1") (pintype "unspecified"))
      (node (ref "R64") (pin "1") (pinfunction "1_1") (pintype "unspecified"))
      (node (ref "U10") (pin "3") (pinfunction "3_3") (pintype "unspecified"))
      (node (ref "U8") (pin "3") (pinfunction "IN_3") (pintype "passive"))
    )
    (net (code "53") (name "Net-(U8-OUT)") (class "Default")
      (node (ref "R59") (pin "1") (pinfunction "1_1") (pintype "unspecified"))
      (node (ref "U8") (pin "1") (pinfunction "OUT_1") (pintype "passive"))
    )
    (net (code "54") (name "Net-(U9-CMP)") (class "Default")
      (node (ref "C16") (pin "1") (pinfunction "1_1") (pintype "unspecified"))
      (node (ref "U9") (pin "3") (pinfunction "CMP_3") (pintype "unspecified"))
    )
    (net (code "55") (name "Net-(U9-EA)") (class "Default")
      (node (ref "C17") (pin "2") (pinfunction "2_2") (pintype "unspecified"))
      (node (ref "R59") (pin "2") (pinfunction "2_2") (pintype "unspecified"))
      (node (ref "U9") (pin "2") (pinfunction "EA_2") (pintype "unspecified"))
    )
    (net (code "56") (name "Net-(U9-FREQ)") (class "Default")
      (node (ref "R60") (pin "2") (pinfunction "2_2") (pintype "unspecified"))
      (node (ref "U9") (pin "6") (pinfunction "FREQ_6") (pintype "unspecified"))
    )
    (net (code "57") (name "Net-(U9-INN)") (class "Default")
      (node (ref "C16") (pin "2") (pinfunction "2_2") (pintype "unspecified"))
      (node (ref "R58") (pin "2") (pinfunction "2_2") (pintype "unspecified"))
      (node (ref "U9") (pin "4") (pinfunction "INN_4") (pintype "unspecified"))
    )
    (net (code "58") (name "Net-(U9-OUT)") (class "Default")
      (node (ref "R61") (pin "1") (pinfunction "1_1") (pintype "unspecified"))
      (node (ref "U9") (pin "8") (pinfunction "OUT_8") (pintype "unspecified"))
    )
    (net (code "59") (name "Vled1") (class "Default")
      (node (ref "C21") (pin "1") (pinfunction "1_1") (pintype "input"))
      (node (ref "D2") (pin "1") (pinfunction "K_1") (pintype "unspecified"))
      (node (ref "D3") (pin "1") (pinfunction "K_1") (pintype "unspecified"))
      (node (ref "J13") (pin "1") (pinfunction "1_1") (pintype "input"))
    )
    (net (code "60") (name "Vled2") (class "Default")
      (node (ref "C22") (pin "1") (pinfunction "1_1") (pintype "input"))
      (node (ref "D4") (pin "1") (pinfunction "K_1") (pintype "unspecified"))
      (node (ref "D5") (pin "1") (pinfunction "K_1") (pintype "unspecified"))
      (node (ref "J14") (pin "1") (pinfunction "1_1") (pintype "input"))
    )
    (net (code "61") (name "Vled3") (class "Default")
      (node (ref "C23") (pin "1") (pinfunction "1_1") (pintype "input"))
      (node (ref "D10") (pin "1") (pinfunction "K_1") (pintype "unspecified"))
      (node (ref "D11") (pin "1") (pinfunction "K_1") (pintype "unspecified"))
      (node (ref "J18") (pin "1") (pinfunction "1_1") (pintype "input"))
    )
    (net (code "62") (name "Vled4") (class "Default")
      (node (ref "C24") (pin "1") (pinfunction "1_1") (pintype "input"))
      (node (ref "D8") (pin "1") (pinfunction "K_1") (pintype "unspecified"))
      (node (ref "D9") (pin "1") (pinfunction "K_1") (pintype "unspecified"))
      (node (ref "J19") (pin "1") (pinfunction "1_1") (pintype "input"))
    )
  )
)
